# CPU.net
KiCad netlist of a schematic drawn in Altium Designer
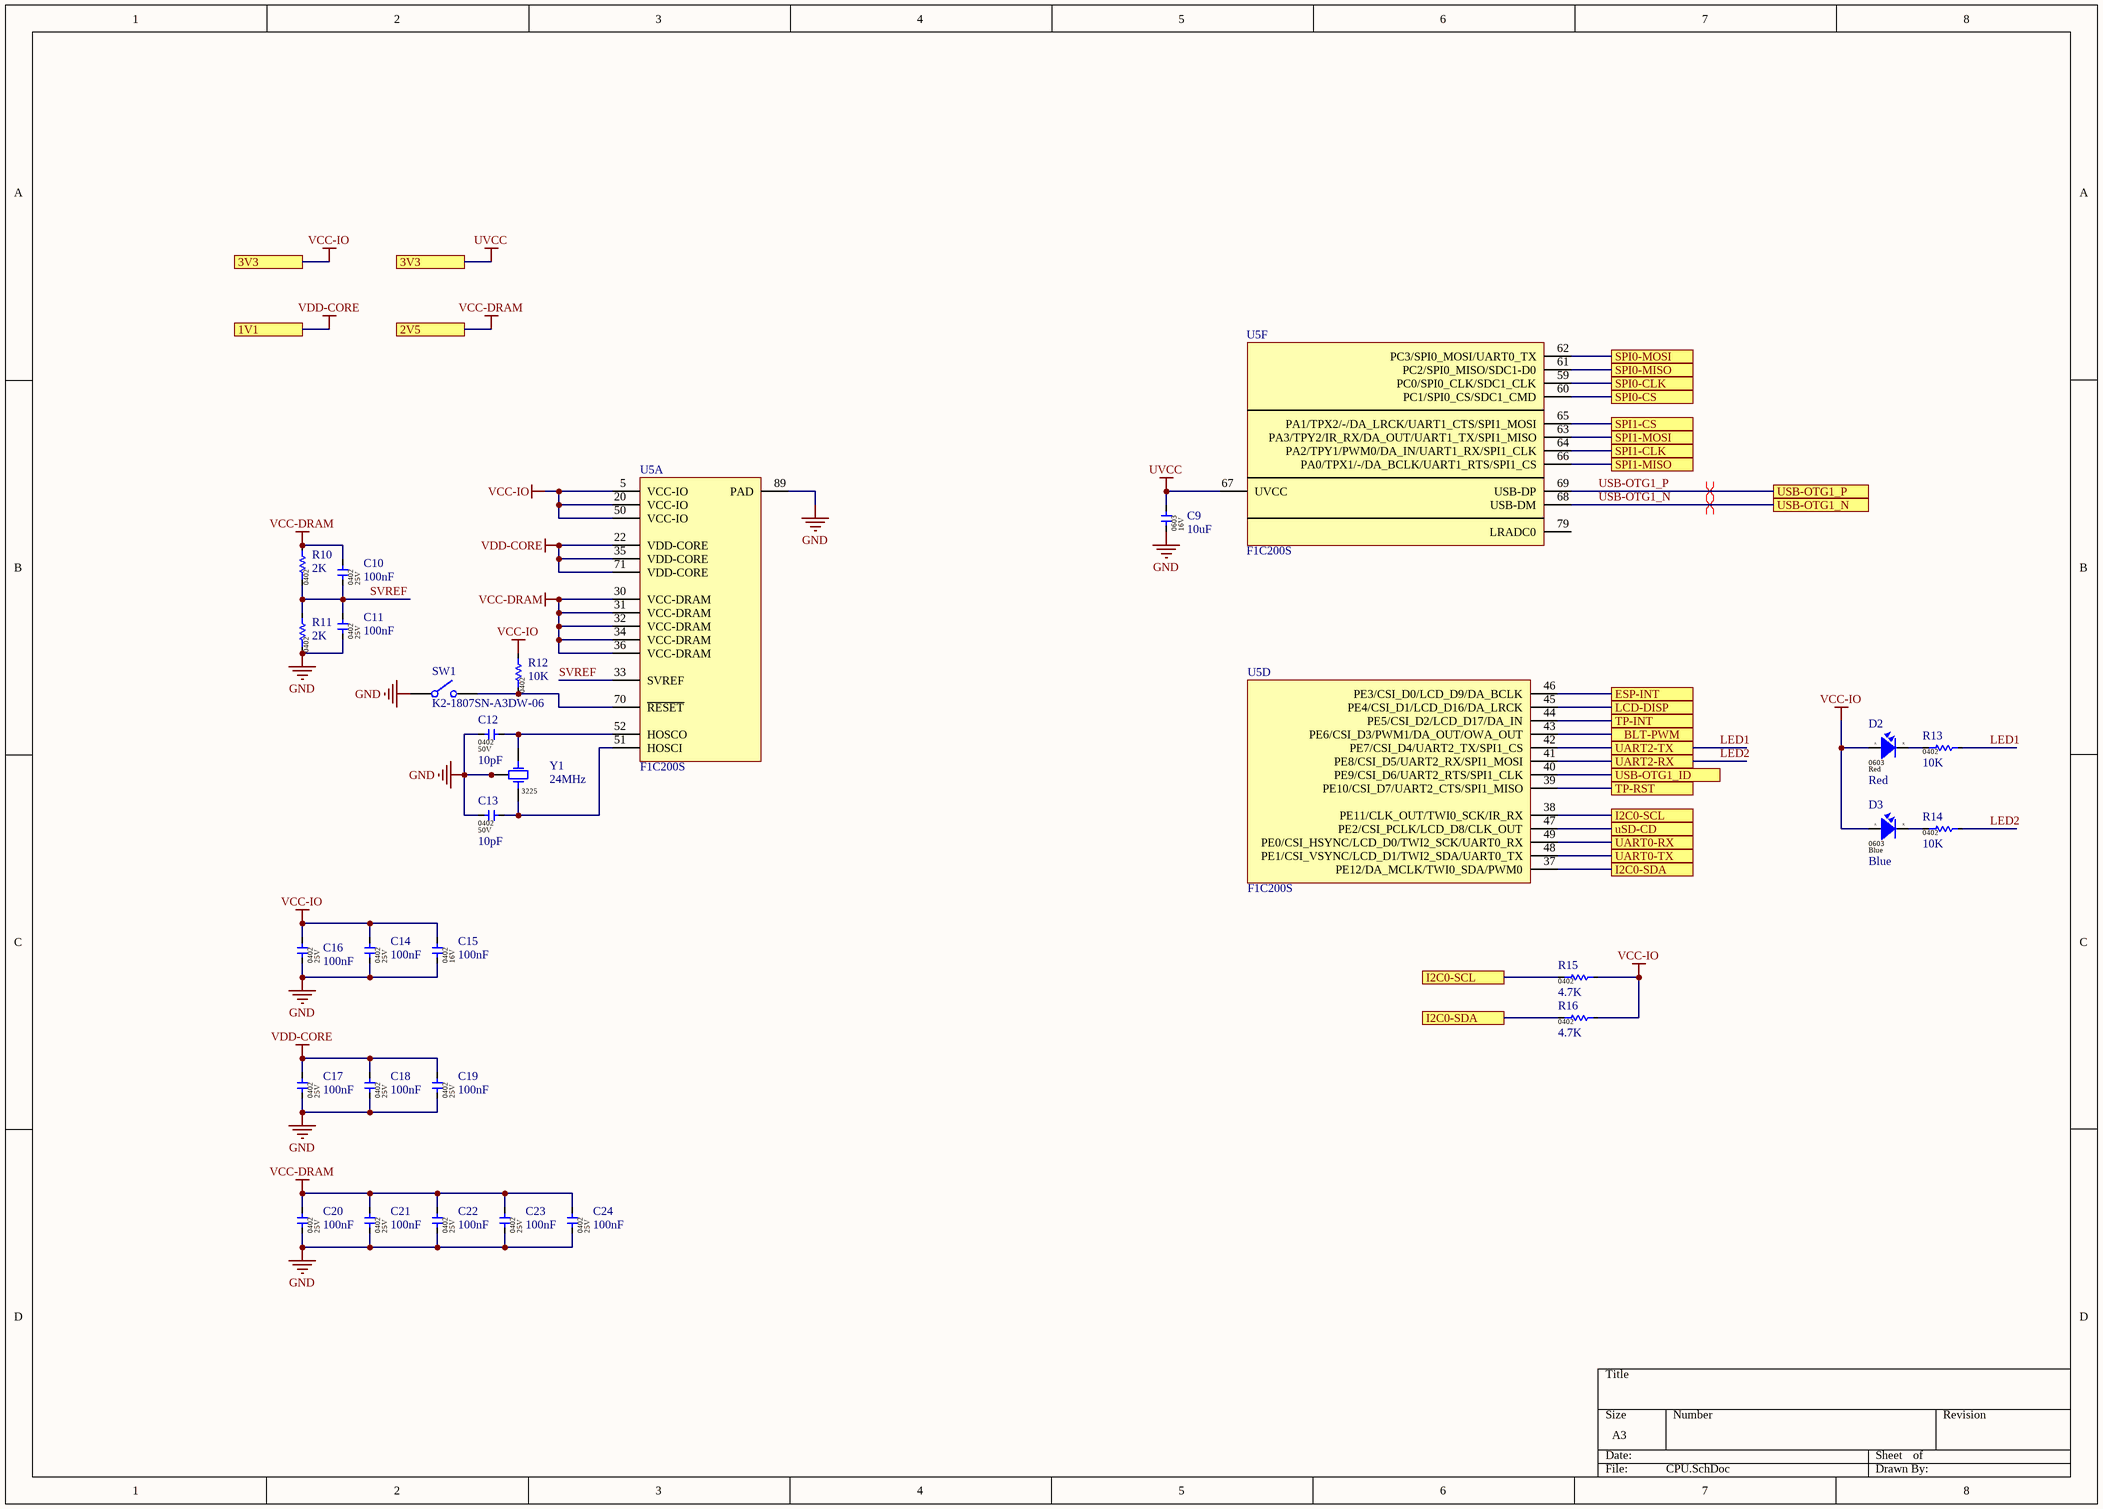
[diagram p0: CPU.SchDoc]

(export (version "E")
  (design (tool "Eeschema 10.0.6"))
  (components
    (comp (ref "C9")
      (value "10uF")
      (footprint "CAP-0603")
      (description "16V 10uF X5R ±20% 0603 Multilayer Ceramic Capacitors MLCC - SMD/SMT ROHS")
      (fields (field (name "MANUFACTURE PART") "0603X106M160CT") (field (name "VOLTAGE") "16V"))
      (libsource (lib "Capacitor Database") (part "Cap-non-polarized"))
    )
    (comp (ref "C10")
      (value "100nF")
      (footprint "CAP-0402")
      (description "100nF ±10% 25V X5R 0402 Multilayer Ceramic Capacitors MLCC - SMD/SMT RoHS")
      (fields (field (name "MANUFACTURE PART") "0402X104K250CT") (field (name "VOLTAGE") "25V"))
      (libsource (lib "Capacitor Database") (part "Cap-non-polarized"))
    )
    (comp (ref "C11")
      (value "100nF")
      (footprint "CAP-0402")
      (description "100nF ±10% 25V X5R 0402 Multilayer Ceramic Capacitors MLCC - SMD/SMT RoHS")
      (fields (field (name "MANUFACTURE PART") "0402X104K250CT") (field (name "VOLTAGE") "25V"))
      (libsource (lib "Capacitor Database") (part "Cap-non-polarized"))
    )
    (comp (ref "C12")
      (value "10pF")
      (footprint "CAP-0402")
      (description "10pF ±5% 50V NP0 0402 Multilayer Ceramic Capacitors MLCC - SMD/SMT RoHS")
      (fields (field (name "MANUFACTURE PART") "0402N100J500CT") (field (name "VOLTAGE") "50V"))
      (libsource (lib "Capacitor Database") (part "Cap-non-polarized"))
    )
    (comp (ref "C13")
      (value "10pF")
      (footprint "CAP-0402")
      (description "10pF ±5% 50V NP0 0402 Multilayer Ceramic Capacitors MLCC - SMD/SMT RoHS")
      (fields (field (name "MANUFACTURE PART") "0402N100J500CT") (field (name "VOLTAGE") "50V"))
      (libsource (lib "Capacitor Database") (part "Cap-non-polarized"))
    )
    (comp (ref "C14")
      (value "100nF")
      (footprint "CAP-0402")
      (description "100nF ±10% 25V X5R 0402 Multilayer Ceramic Capacitors MLCC - SMD/SMT RoHS")
      (fields (field (name "MANUFACTURE PART") "0402X104K250CT") (field (name "VOLTAGE") "25V"))
      (libsource (lib "Capacitor Database") (part "Cap-non-polarized"))
    )
    (comp (ref "C15")
      (value "100nF")
      (footprint "CAP-0402")
      (description "100nF ±10% 16V X7R 0402 Multilayer Ceramic Capacitors MLCC - SMD/SMT RoHS")
      (fields (field (name "MANUFACTURE PART") "0402B104K160CT") (field (name "VOLTAGE") "16V"))
      (libsource (lib "Capacitor Database") (part "Cap-non-polarized"))
    )
    (comp (ref "C16")
      (value "100nF")
      (footprint "CAP-0402")
      (description "100nF ±10% 25V X5R 0402 Multilayer Ceramic Capacitors MLCC - SMD/SMT RoHS")
      (fields (field (name "MANUFACTURE PART") "0402X104K250CT") (field (name "VOLTAGE") "25V"))
      (libsource (lib "Capacitor Database") (part "Cap-non-polarized"))
    )
    (comp (ref "C17")
      (value "100nF")
      (footprint "CAP-0402")
      (description "100nF ±10% 25V X5R 0402 Multilayer Ceramic Capacitors MLCC - SMD/SMT RoHS")
      (fields (field (name "MANUFACTURE PART") "0402X104K250CT") (field (name "VOLTAGE") "25V"))
      (libsource (lib "Capacitor Database") (part "Cap-non-polarized"))
    )
    (comp (ref "C18")
      (value "100nF")
      (footprint "CAP-0402")
      (description "100nF ±10% 25V X5R 0402 Multilayer Ceramic Capacitors MLCC - SMD/SMT RoHS")
      (fields (field (name "MANUFACTURE PART") "0402X104K250CT") (field (name "VOLTAGE") "25V"))
      (libsource (lib "Capacitor Database") (part "Cap-non-polarized"))
    )
    (comp (ref "C19")
      (value "100nF")
      (footprint "CAP-0402")
      (description "100nF ±10% 25V X5R 0402 Multilayer Ceramic Capacitors MLCC - SMD/SMT RoHS")
      (fields (field (name "MANUFACTURE PART") "0402X104K250CT") (field (name "VOLTAGE") "25V"))
      (libsource (lib "Capacitor Database") (part "Cap-non-polarized"))
    )
    (comp (ref "C20")
      (value "100nF")
      (footprint "CAP-0402")
      (description "100nF ±10% 25V X5R 0402 Multilayer Ceramic Capacitors MLCC - SMD/SMT RoHS")
      (fields (field (name "MANUFACTURE PART") "0402X104K250CT") (field (name "VOLTAGE") "25V"))
      (libsource (lib "Capacitor Database") (part "Cap-non-polarized"))
    )
    (comp (ref "C21")
      (value "100nF")
      (footprint "CAP-0402")
      (description "100nF ±10% 25V X5R 0402 Multilayer Ceramic Capacitors MLCC - SMD/SMT RoHS")
      (fields (field (name "MANUFACTURE PART") "0402X104K250CT") (field (name "VOLTAGE") "25V"))
      (libsource (lib "Capacitor Database") (part "Cap-non-polarized"))
    )
    (comp (ref "C22")
      (value "100nF")
      (footprint "CAP-0402")
      (description "100nF ±10% 25V X5R 0402 Multilayer Ceramic Capacitors MLCC - SMD/SMT RoHS")
      (fields (field (name "MANUFACTURE PART") "0402X104K250CT") (field (name "VOLTAGE") "25V"))
      (libsource (lib "Capacitor Database") (part "Cap-non-polarized"))
    )
    (comp (ref "C23")
      (value "100nF")
      (footprint "CAP-0402")
      (description "100nF ±10% 25V X5R 0402 Multilayer Ceramic Capacitors MLCC - SMD/SMT RoHS")
      (fields (field (name "MANUFACTURE PART") "0402X104K250CT") (field (name "VOLTAGE") "25V"))
      (libsource (lib "Capacitor Database") (part "Cap-non-polarized"))
    )
    (comp (ref "C24")
      (value "100nF")
      (footprint "CAP-0402")
      (description "100nF ±10% 25V X5R 0402 Multilayer Ceramic Capacitors MLCC - SMD/SMT RoHS")
      (fields (field (name "MANUFACTURE PART") "0402X104K250CT") (field (name "VOLTAGE") "25V"))
      (libsource (lib "Capacitor Database") (part "Cap-non-polarized"))
    )
    (comp (ref "D2")
      (value "Red")
      (footprint "LED-0603 RED")
      (description "Red 617.5~633.5nm 0603 Light Emitting Diodes (LED) RoHS")
      (fields (field (name "MANUFACTURE PART") "19-217/R6C-AL1M2VY/3T"))
      (libsource (lib "Led Database") (part "Led"))
    )
    (comp (ref "D3")
      (value "Blue")
      (footprint "LED-0603 BLUE")
      (description "Blue 465~475nm 0603 Light Emitting Diodes (LED) RoHS")
      (fields (field (name "MANUFACTURE PART") "19-217/BHC-ZL1M2RY/3T"))
      (libsource (lib "Led Database") (part "Led"))
    )
    (comp (ref "R10")
      (value "2K")
      (footprint "RES-0402")
      (description "2kΩ ±1% 1/16W ±100ppm/℃ 0402 Chip Resistor - Surface Mount RoHS")
      (fields (field (name "MANUFACTURE PART") "WR04X2001FTL"))
      (libsource (lib "Resistor Database") (part "Resistor"))
    )
    (comp (ref "R11")
      (value "2K")
      (footprint "RES-0402")
      (description "2kΩ ±1% 1/16W ±100ppm/℃ 0402 Chip Resistor - Surface Mount RoHS")
      (fields (field (name "MANUFACTURE PART") "WR04X2001FTL"))
      (libsource (lib "Resistor Database") (part "Resistor"))
    )
    (comp (ref "R12")
      (value "10K")
      (footprint "RES-0402")
      (description "10kΩ ±1% 1/16W ±100ppm/℃ 0402 Chip Resistor - Surface Mount RoHS")
      (fields (field (name "MANUFACTURE PART") "WR04X1002FTL"))
      (libsource (lib "Resistor Database") (part "Resistor"))
    )
    (comp (ref "R13")
      (value "10K")
      (footprint "RES-0402")
      (description "10kΩ ±1% 1/16W ±100ppm/℃ 0402 Chip Resistor - Surface Mount RoHS")
      (fields (field (name "MANUFACTURE PART") "WR04X1002FTL"))
      (libsource (lib "Resistor Database") (part "Resistor"))
    )
    (comp (ref "R14")
      (value "10K")
      (footprint "RES-0402")
      (description "10kΩ ±1% 1/16W ±100ppm/℃ 0402 Chip Resistor - Surface Mount RoHS")
      (fields (field (name "MANUFACTURE PART") "WR04X1002FTL"))
      (libsource (lib "Resistor Database") (part "Resistor"))
    )
    (comp (ref "R15")
      (value "4.7K")
      (footprint "RES-0402")
      (description "4.7kΩ ±1% 1/16W ±100ppm/℃ 0402 Chip Resistor - Surface Mount RoHS")
      (fields (field (name "MANUFACTURE PART") "WR04X4701FTL"))
      (libsource (lib "Resistor Database") (part "Resistor"))
    )
    (comp (ref "R16")
      (value "4.7K")
      (footprint "RES-0402")
      (description "4.7kΩ ±1% 1/16W ±100ppm/℃ 0402 Chip Resistor - Surface Mount RoHS")
      (fields (field (name "MANUFACTURE PART") "WR04X4701FTL"))
      (libsource (lib "Resistor Database") (part "Resistor"))
    )
    (comp (ref "SW1")
      (value "K2-1807SN-A3DW-06")
      (footprint "SW - TYPE 3")
      (description "SMD,3×4×2.0mm Tactile Switches RoHS")
      (libsource (lib "Connectors, Misc") (part "Tactile Switch"))
    )
    (comp (ref "U5")
      (value "F1C200S")
      (footprint "F1Cx00s")
      (description "The Allwinner F1C200s is a small SoC with an ARM926EJ-S CPU core and 64MB of embedded DDR SDRAM.")
      (libsource (lib "IC Database") (part "F1CX00S"))
    )
    (comp (ref "Y1")
      (value "24MHz")
      (footprint "Crystal-3225")
      (description "24MHz ±10ppm 12pF 40Ω SMD-3225 Crystals RoHS")
      (fields (field (name "MANUFACTURE PART") "SX32Y024000BC1T"))
      (libsource (lib "Osc Database") (part "XTAL-4 pin"))
    )
  )
  (nets
    (net (code "1") (name "/BLT-PWM") (class "Default")
      (node (ref "U5") (pin "43") (pinfunction "PE6/CSI_D3/PWM1/DA_OUT/OWA_OUT_43") (pintype "passive"))
    )
    (net (code "2") (name "/ESP-INT") (class "Default")
      (node (ref "U5") (pin "46") (pinfunction "PE3/CSI_D0/LCD_D9/DA_BCLK_46") (pintype "passive"))
    )
    (net (code "3") (name "/I2C0-SCL") (class "Default")
      (node (ref "R15") (pin "1") (pinfunction "1_1") (pintype "passive"))
      (node (ref "U5") (pin "38") (pinfunction "PE11/CLK_OUT/TWI0_SCK/IR_RX_38") (pintype "passive"))
    )
    (net (code "4") (name "/I2C0-SDA") (class "Default")
      (node (ref "R16") (pin "1") (pinfunction "1_1") (pintype "passive"))
      (node (ref "U5") (pin "37") (pinfunction "PE12/DA_MCLK/TWI0_SDA/PWM0_37") (pintype "passive"))
    )
    (net (code "5") (name "/LCD-DISP") (class "Default")
      (node (ref "U5") (pin "45") (pinfunction "PE4/CSI_D1/LCD_D16/DA_LRCK_45") (pintype "passive"))
    )
    (net (code "6") (name "/LED1") (class "Default")
      (node (ref "R13") (pin "2") (pinfunction "2_2") (pintype "passive"))
      (node (ref "U5") (pin "42") (pinfunction "PE7/CSI_D4/UART2_TX/SPI1_CS_42") (pintype "passive"))
    )
    (net (code "7") (name "/LED2") (class "Default")
      (node (ref "R14") (pin "2") (pinfunction "2_2") (pintype "passive"))
      (node (ref "U5") (pin "41") (pinfunction "PE8/CSI_D5/UART2_RX/SPI1_MOSI_41") (pintype "passive"))
    )
    (net (code "8") (name "/SPI0-CLK") (class "Default")
      (node (ref "U5") (pin "59") (pinfunction "PC0/SPI0_CLK/SDC1_CLK_59") (pintype "passive"))
    )
    (net (code "9") (name "/SPI0-CS") (class "Default")
      (node (ref "U5") (pin "60") (pinfunction "PC1/SPI0_CS/SDC1_CMD_60") (pintype "passive"))
    )
    (net (code "10") (name "/SPI0-MISO") (class "Default")
      (node (ref "U5") (pin "61") (pinfunction "PC2/SPI0_MISO/SDC1-D0_61") (pintype "passive"))
    )
    (net (code "11") (name "/SPI0-MOSI") (class "Default")
      (node (ref "U5") (pin "62") (pinfunction "PC3/SPI0_MOSI/UART0_TX_62") (pintype "passive"))
    )
    (net (code "12") (name "/SPI1-CLK") (class "Default")
      (node (ref "U5") (pin "64") (pinfunction "PA2/TPY1/PWM0/DA_IN/UART1_RX/SPI1_CLK_64") (pintype "passive"))
    )
    (net (code "13") (name "/SPI1-CS") (class "Default")
      (node (ref "U5") (pin "65") (pinfunction "PA1/TPX2/-/DA_LRCK/UART1_CTS/SPI1_MOSI_65") (pintype "passive"))
    )
    (net (code "14") (name "/SPI1-MISO") (class "Default")
      (node (ref "U5") (pin "66") (pinfunction "PA0/TPX1/-/DA_BCLK/UART1_RTS/SPI1_CS_66") (pintype "passive"))
    )
    (net (code "15") (name "/SPI1-MOSI") (class "Default")
      (node (ref "U5") (pin "63") (pinfunction "PA3/TPY2/IR_RX/DA_OUT/UART1_TX/SPI1_MISO_63") (pintype "passive"))
    )
    (net (code "16") (name "/SVREF") (class "Default")
      (node (ref "C10") (pin "1") (pinfunction "1_1") (pintype "passive"))
      (node (ref "C11") (pin "2") (pinfunction "2_2") (pintype "passive"))
      (node (ref "R10") (pin "1") (pinfunction "1_1") (pintype "passive"))
      (node (ref "R11") (pin "2") (pinfunction "2_2") (pintype "passive"))
      (node (ref "U5") (pin "33") (pinfunction "SVREF_33") (pintype "passive"))
    )
    (net (code "17") (name "/TP-INT") (class "Default")
      (node (ref "U5") (pin "44") (pinfunction "PE5/CSI_D2/LCD_D17/DA_IN_44") (pintype "passive"))
    )
    (net (code "18") (name "/TP-RST") (class "Default")
      (node (ref "U5") (pin "39") (pinfunction "PE10/CSI_D7/UART2_CTS/SPI1_MISO_39") (pintype "passive"))
    )
    (net (code "19") (name "/UART0-RX") (class "Default")
      (node (ref "U5") (pin "49") (pinfunction "PE0/CSI_HSYNC/LCD_D0/TWI2_SCK/UART0_RX_49") (pintype "passive"))
    )
    (net (code "20") (name "/UART0-TX") (class "Default")
      (node (ref "U5") (pin "48") (pinfunction "PE1/CSI_VSYNC/LCD_D1/TWI2_SDA/UART0_TX_48") (pintype "passive"))
    )
    (net (code "21") (name "/USB-OTG1_ID") (class "Default")
      (node (ref "U5") (pin "40") (pinfunction "PE9/CSI_D6/UART2_RTS/SPI1_CLK_40") (pintype "passive"))
    )
    (net (code "22") (name "/USB-OTG1_N") (class "Default")
      (node (ref "U5") (pin "68") (pinfunction "USB-DM_68") (pintype "passive"))
    )
    (net (code "23") (name "/USB-OTG1_P") (class "Default")
      (node (ref "U5") (pin "69") (pinfunction "USB-DP_69") (pintype "passive"))
    )
    (net (code "24") (name "/uSD-CD") (class "Default")
      (node (ref "U5") (pin "47") (pinfunction "PE2/CSI_PCLK/LCD_D8/CLK_OUT_47") (pintype "passive"))
    )
    (net (code "25") (name "GND") (class "Default")
      (node (ref "C11") (pin "1") (pinfunction "1_1") (pintype "passive"))
      (node (ref "C12") (pin "1") (pinfunction "1_1") (pintype "passive"))
      (node (ref "C13") (pin "1") (pinfunction "1_1") (pintype "passive"))
      (node (ref "C14") (pin "1") (pinfunction "1_1") (pintype "passive"))
      (node (ref "C15") (pin "1") (pinfunction "1_1") (pintype "passive"))
      (node (ref "C16") (pin "1") (pinfunction "1_1") (pintype "passive"))
      (node (ref "C17") (pin "1") (pinfunction "1_1") (pintype "passive"))
      (node (ref "C18") (pin "1") (pinfunction "1_1") (pintype "passive"))
      (node (ref "C19") (pin "1") (pinfunction "1_1") (pintype "passive"))
      (node (ref "C20") (pin "1") (pinfunction "1_1") (pintype "passive"))
      (node (ref "C21") (pin "1") (pinfunction "1_1") (pintype "passive"))
      (node (ref "C22") (pin "1") (pinfunction "1_1") (pintype "passive"))
      (node (ref "C23") (pin "1") (pinfunction "1_1") (pintype "passive"))
      (node (ref "C24") (pin "1") (pinfunction "1_1") (pintype "passive"))
      (node (ref "C9") (pin "1") (pinfunction "1_1") (pintype "passive"))
      (node (ref "R11") (pin "1") (pinfunction "1_1") (pintype "passive"))
      (node (ref "SW1") (pin "1") (pintype "passive"))
      (node (ref "U5") (pin "89") (pinfunction "PAD_89") (pintype "passive"))
      (node (ref "Y1") (pin "2") (pinfunction "GND_2") (pintype "power_in"))
      (node (ref "Y1") (pin "4") (pinfunction "GND_4") (pintype "power_in"))
    )
    (net (code "26") (name "Net-(D2-Cathode)") (class "Default")
      (node (ref "D2") (pin "1") (pinfunction "Cathode_1") (pintype "passive"))
      (node (ref "R13") (pin "1") (pinfunction "1_1") (pintype "passive"))
    )
    (net (code "27") (name "Net-(D3-Cathode)") (class "Default")
      (node (ref "D3") (pin "1") (pinfunction "Cathode_1") (pintype "passive"))
      (node (ref "R14") (pin "1") (pinfunction "1_1") (pintype "passive"))
    )
    (net (code "28") (name "Net-(U5A-HOSCI)") (class "Default")
      (node (ref "C13") (pin "2") (pinfunction "2_2") (pintype "passive"))
      (node (ref "U5") (pin "51") (pinfunction "HOSCI_51") (pintype "passive"))
      (node (ref "Y1") (pin "3") (pinfunction "X2_3") (pintype "passive"))
    )
    (net (code "29") (name "Net-(U5A-HOSCO)") (class "Default")
      (node (ref "C12") (pin "2") (pinfunction "2_2") (pintype "passive"))
      (node (ref "U5") (pin "52") (pinfunction "HOSCO_52") (pintype "passive"))
      (node (ref "Y1") (pin "1") (pinfunction "X1_1") (pintype "passive"))
    )
    (net (code "30") (name "Net-(U5A-~{RESET})") (class "Default")
      (node (ref "R12") (pin "1") (pinfunction "1_1") (pintype "passive"))
      (node (ref "SW1") (pin "2") (pintype "passive"))
      (node (ref "U5") (pin "70") (pinfunction "~{RESET}_70") (pintype "passive"))
    )
    (net (code "31") (name "UVCC") (class "Default")
      (node (ref "C14") (pin "2") (pinfunction "2_2") (pintype "passive"))
      (node (ref "C15") (pin "2") (pinfunction "2_2") (pintype "passive"))
      (node (ref "C16") (pin "2") (pinfunction "2_2") (pintype "passive"))
      (node (ref "C9") (pin "2") (pinfunction "2_2") (pintype "passive"))
      (node (ref "D2") (pin "2") (pinfunction "Anode_2") (pintype "passive"))
      (node (ref "D3") (pin "2") (pinfunction "Anode_2") (pintype "passive"))
      (node (ref "R12") (pin "2") (pinfunction "2_2") (pintype "passive"))
      (node (ref "R15") (pin "2") (pinfunction "2_2") (pintype "passive"))
      (node (ref "R16") (pin "2") (pinfunction "2_2") (pintype "passive"))
      (node (ref "U5") (pin "20") (pinfunction "VCC-IO_20") (pintype "passive"))
      (node (ref "U5") (pin "5") (pinfunction "VCC-IO_5") (pintype "passive"))
      (node (ref "U5") (pin "50") (pinfunction "VCC-IO_50") (pintype "passive"))
      (node (ref "U5") (pin "67") (pinfunction "UVCC_67") (pintype "passive"))
    )
    (net (code "32") (name "VCC-DRAM") (class "Default")
      (node (ref "C10") (pin "2") (pinfunction "2_2") (pintype "passive"))
      (node (ref "C20") (pin "2") (pinfunction "2_2") (pintype "passive"))
      (node (ref "C21") (pin "2") (pinfunction "2_2") (pintype "passive"))
      (node (ref "C22") (pin "2") (pinfunction "2_2") (pintype "passive"))
      (node (ref "C23") (pin "2") (pinfunction "2_2") (pintype "passive"))
      (node (ref "C24") (pin "2") (pinfunction "2_2") (pintype "passive"))
      (node (ref "R10") (pin "2") (pinfunction "2_2") (pintype "passive"))
      (node (ref "U5") (pin "30") (pinfunction "VCC-DRAM_30") (pintype "passive"))
      (node (ref "U5") (pin "31") (pinfunction "VCC-DRAM_31") (pintype "passive"))
      (node (ref "U5") (pin "32") (pinfunction "VCC-DRAM_32") (pintype "passive"))
      (node (ref "U5") (pin "34") (pinfunction "VCC-DRAM_34") (pintype "passive"))
      (node (ref "U5") (pin "36") (pinfunction "VCC-DRAM_36") (pintype "passive"))
    )
    (net (code "33") (name "VDD-CORE") (class "Default")
      (node (ref "C17") (pin "2") (pinfunction "2_2") (pintype "passive"))
      (node (ref "C18") (pin "2") (pinfunction "2_2") (pintype "passive"))
      (node (ref "C19") (pin "2") (pinfunction "2_2") (pintype "passive"))
      (node (ref "U5") (pin "22") (pinfunction "VDD-CORE_22") (pintype "passive"))
      (node (ref "U5") (pin "35") (pinfunction "VDD-CORE_35") (pintype "passive"))
      (node (ref "U5") (pin "71") (pinfunction "VDD-CORE_71") (pintype "passive"))
    )
    (net (code "34") (name "unconnected-(U5F-LRADC0-Pad79)") (class "Default")
      (node (ref "U5") (pin "79") (pinfunction "LRADC0_79") (pintype "passive"))
    )
  )
)
